# CS4354_breakout.net
KiCad netlist of a schematic drawn in EAGLE
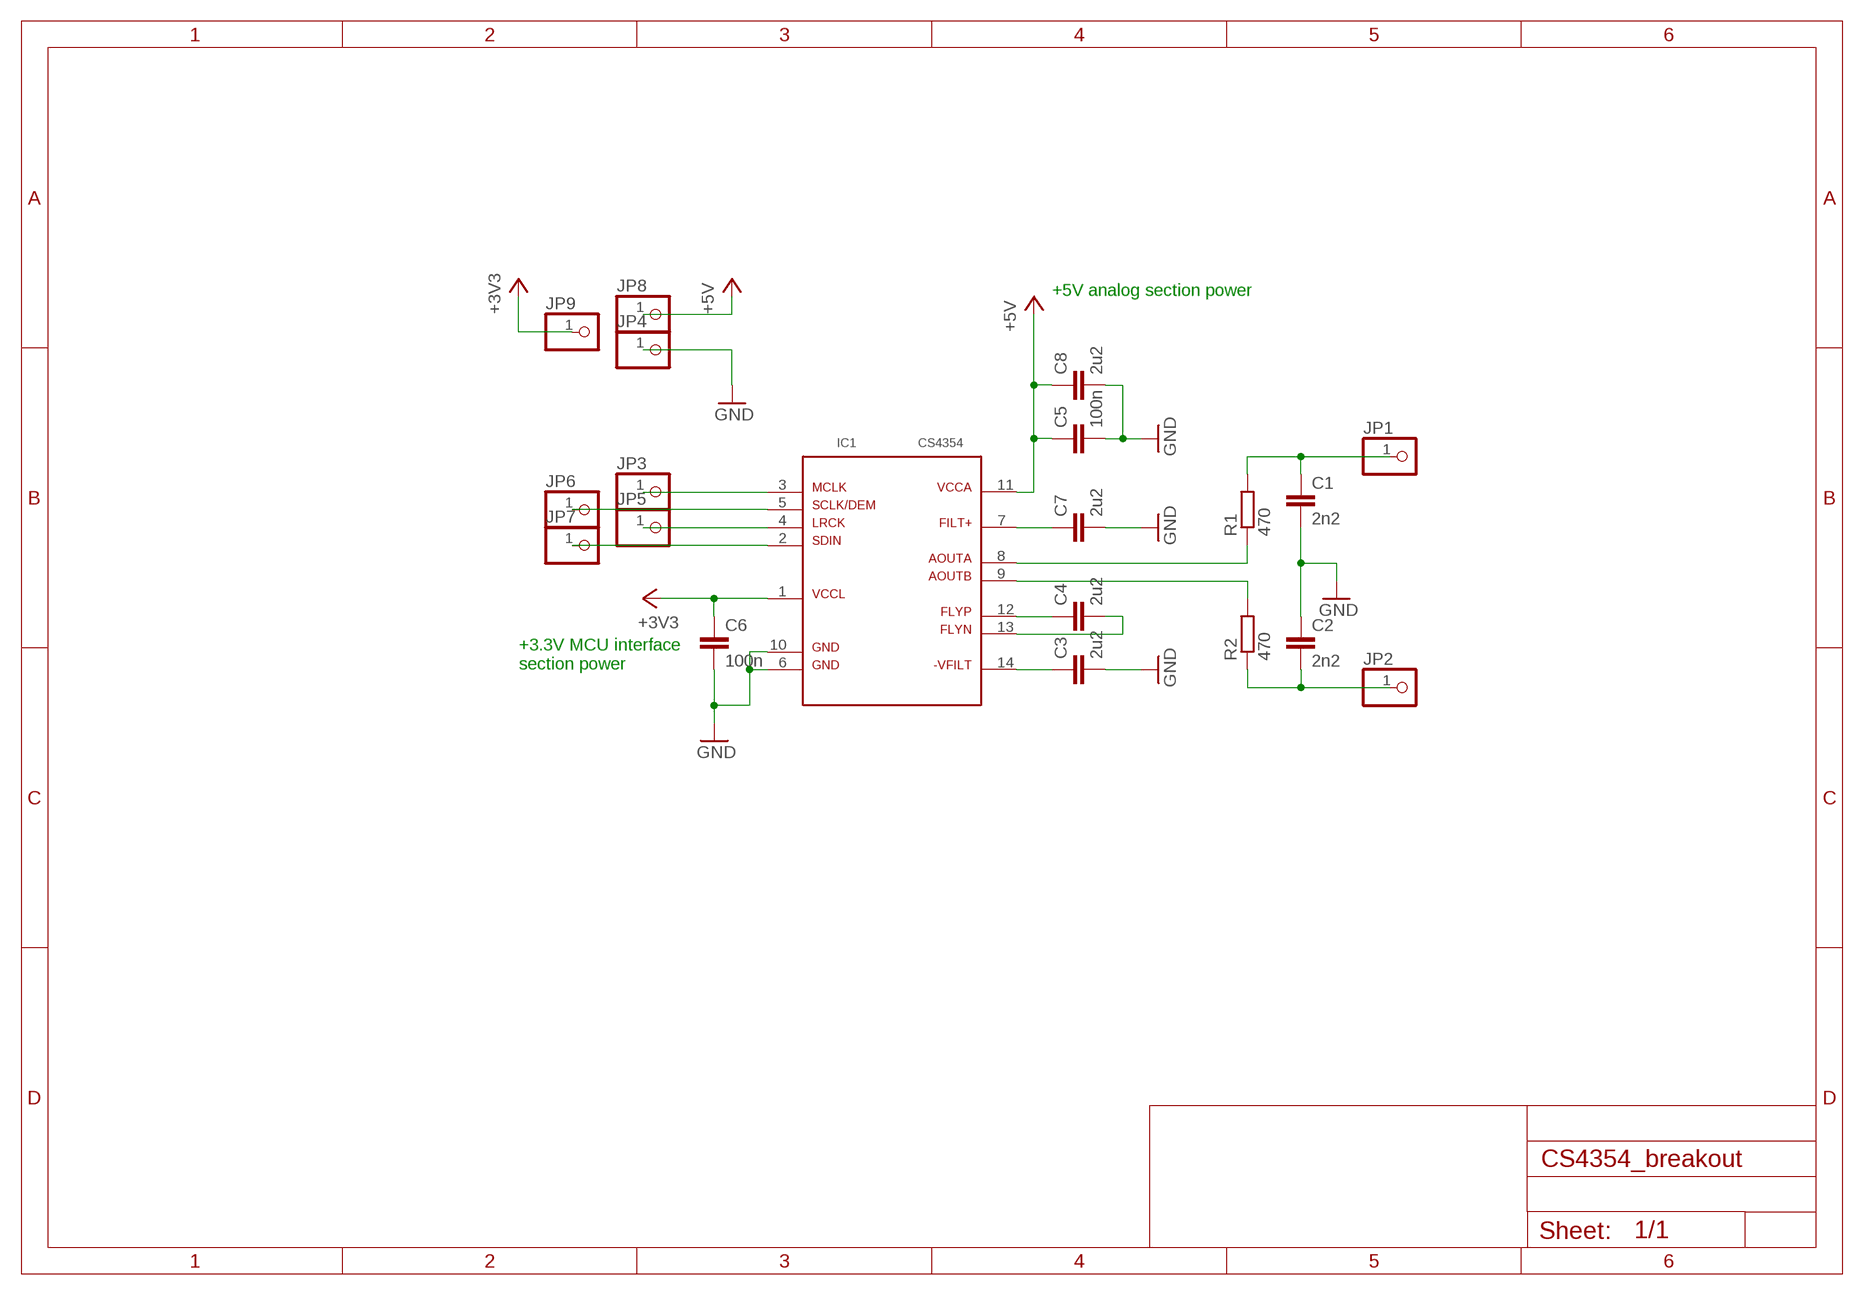
[diagram p0: schematic, sheet 1]

(export (version "E")
  (design (tool "Eeschema 10.0.6"))
  (components
    (comp (ref "C1")
      (value "2n2")
      (footprint "eagle-import:C0603K")
      (libsource (lib "eagle-import") (part "C-EUC0603K"))
    )
    (comp (ref "C2")
      (value "2n2")
      (footprint "eagle-import:C0603K")
      (libsource (lib "eagle-import") (part "C-EUC0603K"))
    )
    (comp (ref "C3")
      (value "2u2")
      (footprint "eagle-import:C0603K")
      (libsource (lib "eagle-import") (part "C-EUC0603K"))
    )
    (comp (ref "C4")
      (value "2u2")
      (footprint "eagle-import:C0603K")
      (libsource (lib "eagle-import") (part "C-EUC0603K"))
    )
    (comp (ref "C5")
      (value "100n")
      (footprint "eagle-import:C0603K")
      (libsource (lib "eagle-import") (part "C-EUC0603K"))
    )
    (comp (ref "C6")
      (value "100n")
      (footprint "eagle-import:C0603K")
      (libsource (lib "eagle-import") (part "C-EUC0603K"))
    )
    (comp (ref "C7")
      (value "2u2")
      (footprint "eagle-import:C0603K")
      (libsource (lib "eagle-import") (part "C-EUC0603K"))
    )
    (comp (ref "C8")
      (value "2u2")
      (footprint "eagle-import:C0603K")
      (libsource (lib "eagle-import") (part "C-EUC0603K"))
    )
    (comp (ref "IC1")
      (value "CS4354")
      (footprint "eagle-import:SO14")
      (libsource (lib "eagle-import") (part "CS4354"))
    )
    (comp (ref "JP1")
      (value "PINHD-1X1")
      (footprint "eagle-import:1X01")
      (libsource (lib "eagle-import") (part "PINHD-1X1"))
    )
    (comp (ref "JP2")
      (value "PINHD-1X1")
      (footprint "eagle-import:1X01")
      (libsource (lib "eagle-import") (part "PINHD-1X1"))
    )
    (comp (ref "JP3")
      (value "PINHD-1X1")
      (footprint "eagle-import:1X01")
      (libsource (lib "eagle-import") (part "PINHD-1X1"))
    )
    (comp (ref "JP4")
      (value "PINHD-1X1")
      (footprint "eagle-import:1X01")
      (libsource (lib "eagle-import") (part "PINHD-1X1"))
    )
    (comp (ref "JP5")
      (value "PINHD-1X1")
      (footprint "eagle-import:1X01")
      (libsource (lib "eagle-import") (part "PINHD-1X1"))
    )
    (comp (ref "JP6")
      (value "PINHD-1X1")
      (footprint "eagle-import:1X01")
      (libsource (lib "eagle-import") (part "PINHD-1X1"))
    )
    (comp (ref "JP7")
      (value "PINHD-1X1")
      (footprint "eagle-import:1X01")
      (libsource (lib "eagle-import") (part "PINHD-1X1"))
    )
    (comp (ref "JP8")
      (value "PINHD-1X1")
      (footprint "eagle-import:1X01")
      (libsource (lib "eagle-import") (part "PINHD-1X1"))
    )
    (comp (ref "JP9")
      (value "PINHD-1X1")
      (footprint "eagle-import:1X01")
      (libsource (lib "eagle-import") (part "PINHD-1X1"))
    )
    (comp (ref "R1")
      (value "470")
      (footprint "eagle-import:R0603")
      (libsource (lib "eagle-import") (part "R-EU_R0603"))
    )
    (comp (ref "R2")
      (value "470")
      (footprint "eagle-import:R0603")
      (libsource (lib "eagle-import") (part "R-EU_R0603"))
    )
  )
  (nets
    (net (code "1") (name "+3V3") (class "Default")
      (node (ref "C6") (pin "1") (pinfunction "1_1") (pintype "passive"))
      (node (ref "IC1") (pin "1") (pinfunction "P1_1") (pintype "power_in"))
      (node (ref "JP9") (pin "1") (pinfunction "1_1") (pintype "passive"))
    )
    (net (code "2") (name "+5V") (class "Default")
      (node (ref "C5") (pin "1") (pinfunction "1_1") (pintype "passive"))
      (node (ref "C8") (pin "1") (pinfunction "1_1") (pintype "passive"))
      (node (ref "IC1") (pin "11") (pinfunction "P11_11") (pintype "power_in"))
      (node (ref "JP8") (pin "1") (pinfunction "1_1") (pintype "passive"))
    )
    (net (code "3") (name "GND") (class "Default")
      (node (ref "C1") (pin "2") (pinfunction "2_2") (pintype "passive"))
      (node (ref "C2") (pin "1") (pinfunction "1_1") (pintype "passive"))
      (node (ref "C3") (pin "2") (pinfunction "2_2") (pintype "passive"))
      (node (ref "C5") (pin "2") (pinfunction "2_2") (pintype "passive"))
      (node (ref "C6") (pin "2") (pinfunction "2_2") (pintype "passive"))
      (node (ref "C7") (pin "2") (pinfunction "2_2") (pintype "passive"))
      (node (ref "C8") (pin "2") (pinfunction "2_2") (pintype "passive"))
      (node (ref "IC1") (pin "10") (pinfunction "P10_10") (pintype "power_in"))
      (node (ref "IC1") (pin "6") (pinfunction "P6_6") (pintype "power_in"))
      (node (ref "JP4") (pin "1") (pinfunction "1_1") (pintype "passive"))
    )
    (net (code "4") (name "Net-(C1-Pad1)") (class "Default")
      (node (ref "C1") (pin "1") (pinfunction "1_1") (pintype "passive"))
      (node (ref "JP1") (pin "1") (pinfunction "1_1") (pintype "passive"))
      (node (ref "R1") (pin "2") (pinfunction "2_2") (pintype "passive"))
    )
    (net (code "5") (name "Net-(C2-Pad2)") (class "Default")
      (node (ref "C2") (pin "2") (pinfunction "2_2") (pintype "passive"))
      (node (ref "JP2") (pin "1") (pinfunction "1_1") (pintype "passive"))
      (node (ref "R2") (pin "1") (pinfunction "1_1") (pintype "passive"))
    )
    (net (code "6") (name "Net-(IC1-P2)") (class "Default")
      (node (ref "IC1") (pin "2") (pinfunction "P2_2") (pintype "input"))
      (node (ref "JP7") (pin "1") (pinfunction "1_1") (pintype "passive"))
    )
    (net (code "7") (name "Net-(IC1-P3)") (class "Default")
      (node (ref "IC1") (pin "3") (pinfunction "P3_3") (pintype "input"))
      (node (ref "JP3") (pin "1") (pinfunction "1_1") (pintype "passive"))
    )
    (net (code "8") (name "Net-(IC1-P4)") (class "Default")
      (node (ref "IC1") (pin "4") (pinfunction "P4_4") (pintype "input"))
      (node (ref "JP5") (pin "1") (pinfunction "1_1") (pintype "passive"))
    )
    (net (code "9") (name "Net-(IC1-P5)") (class "Default")
      (node (ref "IC1") (pin "5") (pinfunction "P5_5") (pintype "input"))
      (node (ref "JP6") (pin "1") (pinfunction "1_1") (pintype "passive"))
    )
    (net (code "10") (name "Net-(IC1-P7)") (class "Default")
      (node (ref "C7") (pin "1") (pinfunction "1_1") (pintype "passive"))
      (node (ref "IC1") (pin "7") (pinfunction "P7_7") (pintype "bidirectional"))
    )
    (net (code "11") (name "Net-(IC1-P8)") (class "Default")
      (node (ref "IC1") (pin "8") (pinfunction "P8_8") (pintype "output"))
      (node (ref "R1") (pin "1") (pinfunction "1_1") (pintype "passive"))
    )
    (net (code "12") (name "Net-(IC1-P9)") (class "Default")
      (node (ref "IC1") (pin "9") (pinfunction "P9_9") (pintype "output"))
      (node (ref "R2") (pin "2") (pinfunction "2_2") (pintype "passive"))
    )
    (net (code "13") (name "Net-(IC1-P12)") (class "Default")
      (node (ref "C4") (pin "1") (pinfunction "1_1") (pintype "passive"))
      (node (ref "IC1") (pin "12") (pinfunction "P12_12") (pintype "bidirectional"))
    )
    (net (code "14") (name "Net-(IC1-P13)") (class "Default")
      (node (ref "C4") (pin "2") (pinfunction "2_2") (pintype "passive"))
      (node (ref "IC1") (pin "13") (pinfunction "P13_13") (pintype "bidirectional"))
    )
    (net (code "15") (name "Net-(IC1-P14)") (class "Default")
      (node (ref "C3") (pin "1") (pinfunction "1_1") (pintype "passive"))
      (node (ref "IC1") (pin "14") (pinfunction "P14_14") (pintype "bidirectional"))
    )
  )
)
